# Adafruit_PiCowbell_CAN_Bus.net
KiCad netlist of a schematic drawn in EAGLE
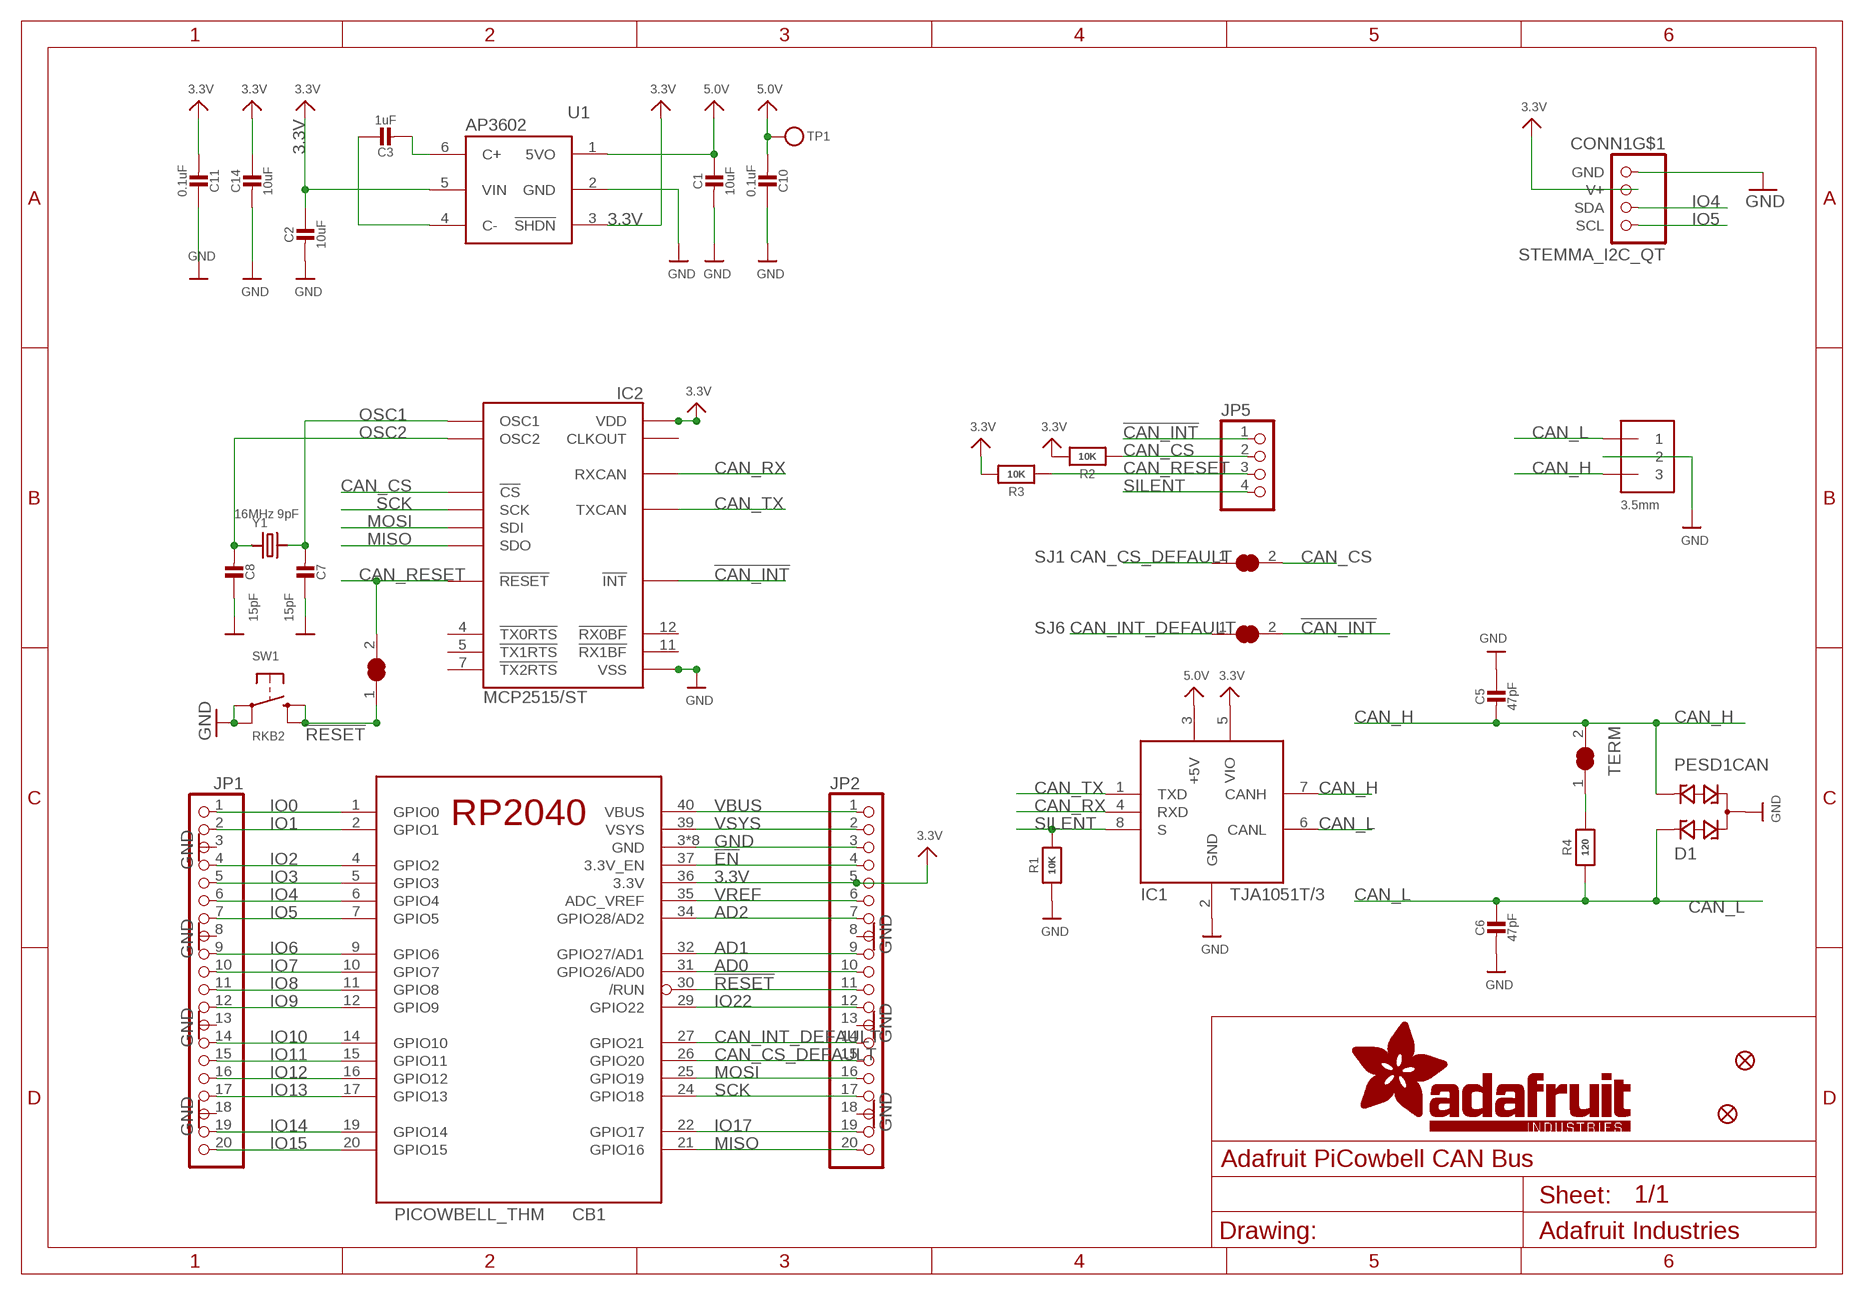
[diagram p0: schematic, sheet 1]

(export (version "E")
  (design (tool "Eeschema 10.0.6"))
  (components
    (comp (ref "C1")
      (value "10uF")
      (footprint "eagle-import:0805-NO")
      (libsource (lib "eagle-import") (part "CAP_CERAMIC0805-NOOUTLINE"))
    )
    (comp (ref "C2")
      (value "10uF")
      (footprint "eagle-import:0805-NO")
      (libsource (lib "eagle-import") (part "CAP_CERAMIC0805-NOOUTLINE"))
    )
    (comp (ref "C3")
      (value "1uF")
      (footprint "eagle-import:0805-NO")
      (libsource (lib "eagle-import") (part "CAP_CERAMIC0805-NOOUTLINE"))
    )
    (comp (ref "C5")
      (value "47pF")
      (footprint "eagle-import:0603-NO")
      (libsource (lib "eagle-import") (part "CAP_CERAMIC0603_NO"))
    )
    (comp (ref "C6")
      (value "47pF")
      (footprint "eagle-import:0603-NO")
      (libsource (lib "eagle-import") (part "CAP_CERAMIC0603_NO"))
    )
    (comp (ref "C7")
      (value "15pF")
      (footprint "eagle-import:0603-NO")
      (libsource (lib "eagle-import") (part "CAP_CERAMIC0603_NO"))
    )
    (comp (ref "C8")
      (value "15pF")
      (footprint "eagle-import:0603-NO")
      (libsource (lib "eagle-import") (part "CAP_CERAMIC0603_NO"))
    )
    (comp (ref "C10")
      (value "0.1uF")
      (footprint "eagle-import:0603-NO")
      (libsource (lib "eagle-import") (part "CAP_CERAMIC0603_NO"))
    )
    (comp (ref "C11")
      (value "0.1uF")
      (footprint "eagle-import:0603-NO")
      (libsource (lib "eagle-import") (part "CAP_CERAMIC0603_NO"))
    )
    (comp (ref "C14")
      (value "10uF")
      (footprint "eagle-import:0805-NO")
      (libsource (lib "eagle-import") (part "CAP_CERAMIC0805-NOOUTLINE"))
    )
    (comp (ref "CAN")
      (value "3.5mm")
      (footprint "eagle-import:TERMBLOCK_1X3-3.5MM")
      (libsource (lib "eagle-import") (part "TERMBLOCK_1X3"))
    )
    (comp (ref "CB1")
      (value "PICOWBELL_THM")
      (footprint "eagle-import:PICOWBELL_THM")
      (libsource (lib "eagle-import") (part "PICOWBELL_THM"))
    )
    (comp (ref "CONN1")
      (value "STEMMA_I2C_QT")
      (footprint "eagle-import:JST_SH4")
      (libsource (lib "eagle-import") (part "STEMMA_I2C_QT"))
    )
    (comp (ref "D1")
      (value "PESD1CAN")
      (footprint "eagle-import:SOT23")
      (libsource (lib "eagle-import") (part "PESD1CAN"))
    )
    (comp (ref "FID1")
      (value "FIDUCIAL_1MM")
      (footprint "eagle-import:FIDUCIAL_1MM")
      (libsource (lib "eagle-import") (part "FIDUCIAL_1MM"))
    )
    (comp (ref "FID2")
      (value "FIDUCIAL_1MM")
      (footprint "eagle-import:FIDUCIAL_1MM")
      (libsource (lib "eagle-import") (part "FIDUCIAL_1MM"))
    )
    (comp (ref "IC1")
      (value "TJA1051T/3")
      (footprint "eagle-import:SOIC8_150MIL")
      (libsource (lib "eagle-import") (part "CAN_TRANSCIEVER_TCAN1051V"))
    )
    (comp (ref "IC2")
      (value "MCP2515/ST")
      (footprint "eagle-import:SSOP20")
      (libsource (lib "eagle-import") (part "MCP2515/ST"))
    )
    (comp (ref "JP1")
      (value "HEADER-1X20_70MIL")
      (footprint "eagle-import:1X20_ROUND_70MIL")
      (libsource (lib "eagle-import") (part "HEADER-1X20_70MIL"))
    )
    (comp (ref "JP2")
      (value "HEADER-1X20_70MIL")
      (footprint "eagle-import:1X20_ROUND_70MIL")
      (libsource (lib "eagle-import") (part "HEADER-1X20_70MIL"))
    )
    (comp (ref "JP5")
      (value "HEADER-1X4ROUND")
      (footprint "eagle-import:1X04_ROUND")
      (libsource (lib "eagle-import") (part "HEADER-1X4ROUND"))
    )
    (comp (ref "R1")
      (value "10K")
      (footprint "eagle-import:0603-NO")
      (libsource (lib "eagle-import") (part "RESISTOR_0603_NOOUT"))
    )
    (comp (ref "R2")
      (value "10K")
      (footprint "eagle-import:0603-NO")
      (libsource (lib "eagle-import") (part "RESISTOR_0603_NOOUT"))
    )
    (comp (ref "R3")
      (value "10K")
      (footprint "eagle-import:0603-NO")
      (libsource (lib "eagle-import") (part "RESISTOR_0603_NOOUT"))
    )
    (comp (ref "R4")
      (value "120")
      (footprint "eagle-import:0603-NO")
      (libsource (lib "eagle-import") (part "RESISTOR_0603_NOOUT"))
    )
    (comp (ref "SJ1")
      (value "SOLDERJUMPER_CLOSED")
      (footprint "eagle-import:SOLDERJUMPER_CLOSEDWIRE")
      (libsource (lib "eagle-import") (part "SOLDERJUMPER_CLOSED"))
    )
    (comp (ref "SJ5")
      (value "SOLDERJUMPER_CLOSED")
      (footprint "eagle-import:SOLDERJUMPER_CLOSEDWIRE")
      (libsource (lib "eagle-import") (part "SOLDERJUMPER_CLOSED"))
    )
    (comp (ref "SJ6")
      (value "SOLDERJUMPER_CLOSED")
      (footprint "eagle-import:SOLDERJUMPER_CLOSEDWIRE")
      (libsource (lib "eagle-import") (part "SOLDERJUMPER_CLOSED"))
    )
    (comp (ref "SW1")
      (value "RKB2")
      (footprint "eagle-import:BTN_RKB2_4.6X2.8")
      (libsource (lib "eagle-import") (part "SWITCH_TACT_SMT_RKB2"))
    )
    (comp (ref "TERM")
      (value "SOLDERJUMPER_CLOSED")
      (footprint "eagle-import:SOLDERJUMPER_CLOSEDWIRE")
      (libsource (lib "eagle-import") (part "SOLDERJUMPER_CLOSED"))
    )
    (comp (ref "TP1")
      (value "TESTPOINTROUND1.5MM")
      (footprint "eagle-import:TESTPOINT_ROUND_1.5MM")
      (libsource (lib "eagle-import") (part "TESTPOINTROUND1.5MM"))
    )
    (comp (ref "U1")
      (value "AP3602")
      (footprint "eagle-import:SOT23-6")
      (libsource (lib "eagle-import") (part "AP3602"))
    )
    (comp (ref "Y1")
      (value "16MHz 9pF")
      (footprint "eagle-import:CRYSTAL_3.2X2.5")
      (libsource (lib "eagle-import") (part "CRYSTAL3.2X2.5"))
    )
  )
  (nets
    (net (code "1") (name "/AD0") (class "Default")
      (node (ref "CB1") (pin "31") (pinfunction "GPIO26/AD0_31") (pintype "bidirectional"))
      (node (ref "JP2") (pin "10") (pinfunction "10_10") (pintype "passive"))
    )
    (net (code "2") (name "/AD1") (class "Default")
      (node (ref "CB1") (pin "32") (pinfunction "GPIO27/AD1_32") (pintype "bidirectional"))
      (node (ref "JP2") (pin "9") (pinfunction "9_9") (pintype "passive"))
    )
    (net (code "3") (name "/AD2") (class "Default")
      (node (ref "CB1") (pin "34") (pinfunction "GPIO28/AD2_34") (pintype "bidirectional"))
      (node (ref "JP2") (pin "7") (pinfunction "7_7") (pintype "passive"))
    )
    (net (code "4") (name "/CAN_CS") (class "Default")
      (node (ref "IC2") (pin "18") (pinfunction "~{CS}_18") (pintype "input"))
      (node (ref "JP5") (pin "2") (pinfunction "2_2") (pintype "passive"))
      (node (ref "R2") (pin "1") (pinfunction "1_1") (pintype "passive"))
      (node (ref "SJ1") (pin "2") (pinfunction "2_2") (pintype "passive"))
    )
    (net (code "5") (name "/CAN_CS_DEFAULT") (class "Default")
      (node (ref "CB1") (pin "26") (pinfunction "GPIO20_26") (pintype "bidirectional"))
      (node (ref "JP2") (pin "15") (pinfunction "15_15") (pintype "passive"))
      (node (ref "SJ1") (pin "1") (pinfunction "1_1") (pintype "passive"))
    )
    (net (code "6") (name "/CAN_H") (class "Default")
      (node (ref "C5") (pin "2") (pinfunction "2_2") (pintype "passive"))
      (node (ref "CAN") (pin "3") (pinfunction "3_3") (pintype "passive"))
      (node (ref "D1") (pin "2") (pinfunction "2_2") (pintype "passive"))
      (node (ref "IC1") (pin "7") (pinfunction "CANH_7") (pintype "bidirectional"))
      (node (ref "TERM") (pin "2") (pinfunction "2_2") (pintype "passive"))
    )
    (net (code "7") (name "/CAN_INT_DEFAULT") (class "Default")
      (node (ref "CB1") (pin "27") (pinfunction "GPIO21_27") (pintype "bidirectional"))
      (node (ref "JP2") (pin "14") (pinfunction "14_14") (pintype "passive"))
      (node (ref "SJ6") (pin "1") (pinfunction "1_1") (pintype "passive"))
    )
    (net (code "8") (name "/CAN_L") (class "Default")
      (node (ref "C6") (pin "1") (pinfunction "1_1") (pintype "passive"))
      (node (ref "CAN") (pin "1") (pinfunction "1_1") (pintype "passive"))
      (node (ref "D1") (pin "1") (pinfunction "1_1") (pintype "passive"))
      (node (ref "IC1") (pin "6") (pinfunction "CANL_6") (pintype "bidirectional"))
      (node (ref "R4") (pin "1") (pinfunction "1_1") (pintype "passive"))
    )
    (net (code "9") (name "/CAN_RESET") (class "Default")
      (node (ref "IC2") (pin "19") (pinfunction "~{RESET}_19") (pintype "input"))
      (node (ref "JP5") (pin "3") (pinfunction "3_3") (pintype "passive"))
      (node (ref "R3") (pin "1") (pinfunction "1_1") (pintype "passive"))
      (node (ref "SJ5") (pin "2") (pinfunction "2_2") (pintype "passive"))
    )
    (net (code "10") (name "/CAN_RX") (class "Default")
      (node (ref "IC1") (pin "4") (pinfunction "RXD_4") (pintype "output"))
      (node (ref "IC2") (pin "2") (pinfunction "RXCAN_2") (pintype "bidirectional"))
    )
    (net (code "11") (name "/CAN_TX") (class "Default")
      (node (ref "IC1") (pin "1") (pinfunction "TXD_1") (pintype "input"))
      (node (ref "IC2") (pin "1") (pinfunction "TXCAN_1") (pintype "bidirectional"))
    )
    (net (code "12") (name "/IO0") (class "Default")
      (node (ref "CB1") (pin "1") (pinfunction "GPIO0_1") (pintype "bidirectional"))
      (node (ref "JP1") (pin "1") (pinfunction "1_1") (pintype "passive"))
    )
    (net (code "13") (name "/IO1") (class "Default")
      (node (ref "CB1") (pin "2") (pinfunction "GPIO1_2") (pintype "bidirectional"))
      (node (ref "JP1") (pin "2") (pinfunction "2_2") (pintype "passive"))
    )
    (net (code "14") (name "/IO2") (class "Default")
      (node (ref "CB1") (pin "4") (pinfunction "GPIO2_4") (pintype "bidirectional"))
      (node (ref "JP1") (pin "4") (pinfunction "4_4") (pintype "passive"))
    )
    (net (code "15") (name "/IO3") (class "Default")
      (node (ref "CB1") (pin "5") (pinfunction "GPIO3_5") (pintype "bidirectional"))
      (node (ref "JP1") (pin "5") (pinfunction "5_5") (pintype "passive"))
    )
    (net (code "16") (name "/IO4") (class "Default")
      (node (ref "CB1") (pin "6") (pinfunction "GPIO4_6") (pintype "bidirectional"))
      (node (ref "CONN1") (pin "3") (pinfunction "SDA_3") (pintype "passive"))
      (node (ref "JP1") (pin "6") (pinfunction "6_6") (pintype "passive"))
    )
    (net (code "17") (name "/IO5") (class "Default")
      (node (ref "CB1") (pin "7") (pinfunction "GPIO5_7") (pintype "bidirectional"))
      (node (ref "CONN1") (pin "4") (pinfunction "SCL_4") (pintype "passive"))
      (node (ref "JP1") (pin "7") (pinfunction "7_7") (pintype "passive"))
    )
    (net (code "18") (name "/IO6") (class "Default")
      (node (ref "CB1") (pin "9") (pinfunction "GPIO6_9") (pintype "bidirectional"))
      (node (ref "JP1") (pin "9") (pinfunction "9_9") (pintype "passive"))
    )
    (net (code "19") (name "/IO7") (class "Default")
      (node (ref "CB1") (pin "10") (pinfunction "GPIO7_10") (pintype "bidirectional"))
      (node (ref "JP1") (pin "10") (pinfunction "10_10") (pintype "passive"))
    )
    (net (code "20") (name "/IO8") (class "Default")
      (node (ref "CB1") (pin "11") (pinfunction "GPIO8_11") (pintype "bidirectional"))
      (node (ref "JP1") (pin "11") (pinfunction "11_11") (pintype "passive"))
    )
    (net (code "21") (name "/IO9") (class "Default")
      (node (ref "CB1") (pin "12") (pinfunction "GPIO9_12") (pintype "bidirectional"))
      (node (ref "JP1") (pin "12") (pinfunction "12_12") (pintype "passive"))
    )
    (net (code "22") (name "/IO10") (class "Default")
      (node (ref "CB1") (pin "14") (pinfunction "GPIO10_14") (pintype "bidirectional"))
      (node (ref "JP1") (pin "14") (pinfunction "14_14") (pintype "passive"))
    )
    (net (code "23") (name "/IO11") (class "Default")
      (node (ref "CB1") (pin "15") (pinfunction "GPIO11_15") (pintype "bidirectional"))
      (node (ref "JP1") (pin "15") (pinfunction "15_15") (pintype "passive"))
    )
    (net (code "24") (name "/IO12") (class "Default")
      (node (ref "CB1") (pin "16") (pinfunction "GPIO12_16") (pintype "bidirectional"))
      (node (ref "JP1") (pin "16") (pinfunction "16_16") (pintype "passive"))
    )
    (net (code "25") (name "/IO13") (class "Default")
      (node (ref "CB1") (pin "17") (pinfunction "GPIO13_17") (pintype "bidirectional"))
      (node (ref "JP1") (pin "17") (pinfunction "17_17") (pintype "passive"))
    )
    (net (code "26") (name "/IO14") (class "Default")
      (node (ref "CB1") (pin "19") (pinfunction "GPIO14_19") (pintype "bidirectional"))
      (node (ref "JP1") (pin "19") (pinfunction "19_19") (pintype "passive"))
    )
    (net (code "27") (name "/IO15") (class "Default")
      (node (ref "CB1") (pin "20") (pinfunction "GPIO15_20") (pintype "bidirectional"))
      (node (ref "JP1") (pin "20") (pinfunction "20_20") (pintype "passive"))
    )
    (net (code "28") (name "/IO17") (class "Default")
      (node (ref "CB1") (pin "22") (pinfunction "GPIO17_22") (pintype "bidirectional"))
      (node (ref "JP2") (pin "19") (pinfunction "19_19") (pintype "passive"))
    )
    (net (code "29") (name "/IO22") (class "Default")
      (node (ref "CB1") (pin "29") (pinfunction "GPIO22_29") (pintype "bidirectional"))
      (node (ref "JP2") (pin "12") (pinfunction "12_12") (pintype "passive"))
    )
    (net (code "30") (name "/MISO") (class "Default")
      (node (ref "CB1") (pin "21") (pinfunction "GPIO16_21") (pintype "bidirectional"))
      (node (ref "IC2") (pin "17") (pinfunction "SDO_17") (pintype "output"))
      (node (ref "JP2") (pin "20") (pinfunction "20_20") (pintype "passive"))
    )
    (net (code "31") (name "/MOSI") (class "Default")
      (node (ref "CB1") (pin "25") (pinfunction "GPIO19_25") (pintype "bidirectional"))
      (node (ref "IC2") (pin "16") (pinfunction "SDI_16") (pintype "input"))
      (node (ref "JP2") (pin "16") (pinfunction "16_16") (pintype "passive"))
    )
    (net (code "32") (name "/OSC1") (class "Default")
      (node (ref "C7") (pin "2") (pinfunction "2_2") (pintype "passive"))
      (node (ref "IC2") (pin "9") (pinfunction "OSC1_9") (pintype "bidirectional"))
      (node (ref "Y1") (pin "2") (pinfunction "2_2") (pintype "passive"))
    )
    (net (code "33") (name "/OSC2") (class "Default")
      (node (ref "C8") (pin "2") (pinfunction "2_2") (pintype "passive"))
      (node (ref "IC2") (pin "8") (pinfunction "OSC2_8") (pintype "bidirectional"))
      (node (ref "Y1") (pin "1") (pinfunction "1_1") (pintype "passive"))
    )
    (net (code "34") (name "/SCK") (class "Default")
      (node (ref "CB1") (pin "24") (pinfunction "GPIO18_24") (pintype "bidirectional"))
      (node (ref "IC2") (pin "14") (pinfunction "SCK_14") (pintype "input"))
      (node (ref "JP2") (pin "17") (pinfunction "17_17") (pintype "passive"))
    )
    (net (code "35") (name "/SILENT") (class "Default")
      (node (ref "IC1") (pin "8") (pinfunction "S_8") (pintype "input"))
      (node (ref "JP5") (pin "4") (pinfunction "4_4") (pintype "passive"))
      (node (ref "R1") (pin "2") (pinfunction "2_2") (pintype "passive"))
    )
    (net (code "36") (name "/VBUS") (class "Default")
      (node (ref "CB1") (pin "40") (pinfunction "VBUS_40") (pintype "power_in"))
      (node (ref "JP2") (pin "1") (pinfunction "1_1") (pintype "passive"))
    )
    (net (code "37") (name "/VREF") (class "Default")
      (node (ref "CB1") (pin "35") (pinfunction "ADC_VREF_35") (pintype "passive"))
      (node (ref "JP2") (pin "6") (pinfunction "6_6") (pintype "passive"))
    )
    (net (code "38") (name "/VSYS") (class "Default")
      (node (ref "CB1") (pin "39") (pinfunction "VSYS_39") (pintype "power_in"))
      (node (ref "JP2") (pin "2") (pinfunction "2_2") (pintype "passive"))
    )
    (net (code "39") (name "/~{CAN_INT}") (class "Default")
      (node (ref "IC2") (pin "13") (pinfunction "~{INT}_13") (pintype "bidirectional"))
      (node (ref "JP5") (pin "1") (pinfunction "1_1") (pintype "passive"))
      (node (ref "SJ6") (pin "2") (pinfunction "2_2") (pintype "passive"))
    )
    (net (code "40") (name "/~{EN}") (class "Default")
      (node (ref "CB1") (pin "37") (pinfunction "3.3V_EN_37") (pintype "passive"))
      (node (ref "JP2") (pin "4") (pinfunction "4_4") (pintype "passive"))
    )
    (net (code "41") (name "/~{RESET}") (class "Default")
      (node (ref "CB1") (pin "30") (pinfunction "/RUN_30") (pintype "bidirectional"))
      (node (ref "JP2") (pin "11") (pinfunction "11_11") (pintype "passive"))
      (node (ref "SJ5") (pin "1") (pinfunction "1_1") (pintype "passive"))
      (node (ref "SW1") (pin "B") (pinfunction "S_B") (pintype "passive"))
      (node (ref "SW1") (pin "B'") (pinfunction "S1_B'") (pintype "passive"))
    )
    (net (code "42") (name "3.3V") (class "Default")
      (node (ref "C11") (pin "2") (pinfunction "2_2") (pintype "passive"))
      (node (ref "C14") (pin "1") (pinfunction "1_1") (pintype "passive"))
      (node (ref "C2") (pin "1") (pinfunction "1_1") (pintype "passive"))
      (node (ref "CB1") (pin "36") (pinfunction "3.3V_36") (pintype "power_in"))
      (node (ref "CONN1") (pin "2") (pinfunction "V+_2") (pintype "passive"))
      (node (ref "IC1") (pin "5") (pinfunction "VIO_5") (pintype "power_in"))
      (node (ref "IC2") (pin "20") (pinfunction "VDD_20") (pintype "power_in"))
      (node (ref "JP2") (pin "5") (pinfunction "5_5") (pintype "passive"))
      (node (ref "R2") (pin "2") (pinfunction "2_2") (pintype "passive"))
      (node (ref "R3") (pin "2") (pinfunction "2_2") (pintype "passive"))
      (node (ref "U1") (pin "3") (pinfunction "~{SHDN}_3") (pintype "input"))
      (node (ref "U1") (pin "5") (pinfunction "VIN_5") (pintype "power_in"))
    )
    (net (code "43") (name "5.0V") (class "Default")
      (node (ref "C1") (pin "1") (pinfunction "1_1") (pintype "passive"))
      (node (ref "C10") (pin "2") (pinfunction "2_2") (pintype "passive"))
      (node (ref "IC1") (pin "3") (pinfunction "+5V_3") (pintype "power_in"))
      (node (ref "TP1") (pin "P$1") (pinfunction "P$1_P$1") (pintype "bidirectional"))
      (node (ref "U1") (pin "1") (pinfunction "5VO_1") (pintype "power_in"))
    )
    (net (code "44") (name "GND") (class "Default")
      (node (ref "C1") (pin "2") (pinfunction "2_2") (pintype "passive"))
      (node (ref "C10") (pin "1") (pinfunction "1_1") (pintype "passive"))
      (node (ref "C11") (pin "1") (pinfunction "1_1") (pintype "passive"))
      (node (ref "C14") (pin "2") (pinfunction "2_2") (pintype "passive"))
      (node (ref "C2") (pin "2") (pinfunction "2_2") (pintype "passive"))
      (node (ref "C5") (pin "1") (pinfunction "1_1") (pintype "passive"))
      (node (ref "C6") (pin "2") (pinfunction "2_2") (pintype "passive"))
      (node (ref "C7") (pin "1") (pinfunction "1_1") (pintype "passive"))
      (node (ref "C8") (pin "1") (pinfunction "1_1") (pintype "passive"))
      (node (ref "CAN") (pin "2") (pinfunction "2_2") (pintype "passive"))
      (node (ref "CB1") (pin "13") (pinfunction "GND_13") (pintype "power_in"))
      (node (ref "CB1") (pin "18") (pinfunction "GND_18") (pintype "power_in"))
      (node (ref "CB1") (pin "23") (pinfunction "GND_23") (pintype "power_in"))
      (node (ref "CB1") (pin "28") (pinfunction "GND_28") (pintype "power_in"))
      (node (ref "CB1") (pin "3") (pinfunction "GND_3") (pintype "power_in"))
      (node (ref "CB1") (pin "33") (pinfunction "GND_33") (pintype "power_in"))
      (node (ref "CB1") (pin "38") (pinfunction "GND_38") (pintype "power_in"))
      (node (ref "CB1") (pin "8") (pinfunction "GND_8") (pintype "power_in"))
      (node (ref "CONN1") (pin "1") (pinfunction "GND_1") (pintype "passive"))
      (node (ref "D1") (pin "3") (pinfunction "3_3") (pintype "passive"))
      (node (ref "IC1") (pin "2") (pinfunction "GND_2") (pintype "power_in"))
      (node (ref "IC2") (pin "10") (pinfunction "VSS_10") (pintype "power_in"))
      (node (ref "JP1") (pin "13") (pinfunction "13_13") (pintype "passive"))
      (node (ref "JP1") (pin "18") (pinfunction "18_18") (pintype "passive"))
      (node (ref "JP1") (pin "3") (pinfunction "3_3") (pintype "passive"))
      (node (ref "JP1") (pin "8") (pinfunction "8_8") (pintype "passive"))
      (node (ref "JP2") (pin "13") (pinfunction "13_13") (pintype "passive"))
      (node (ref "JP2") (pin "18") (pinfunction "18_18") (pintype "passive"))
      (node (ref "JP2") (pin "3") (pinfunction "3_3") (pintype "passive"))
      (node (ref "JP2") (pin "8") (pinfunction "8_8") (pintype "passive"))
      (node (ref "R1") (pin "1") (pinfunction "1_1") (pintype "passive"))
      (node (ref "SW1") (pin "A") (pinfunction "P_A") (pintype "passive"))
      (node (ref "SW1") (pin "A'") (pinfunction "P1_A'") (pintype "passive"))
      (node (ref "U1") (pin "2") (pinfunction "GND_2") (pintype "power_in"))
    )
    (net (code "45") (name "Net-(R4-Pad2)") (class "Default")
      (node (ref "R4") (pin "2") (pinfunction "2_2") (pintype "passive"))
      (node (ref "TERM") (pin "1") (pinfunction "1_1") (pintype "passive"))
    )
    (net (code "46") (name "Net-(U1-C+)") (class "Default")
      (node (ref "C3") (pin "2") (pinfunction "2_2") (pintype "passive"))
      (node (ref "U1") (pin "6") (pinfunction "C+_6") (pintype "bidirectional"))
    )
    (net (code "47") (name "Net-(U1-C-)") (class "Default")
      (node (ref "C3") (pin "1") (pinfunction "1_1") (pintype "passive"))
      (node (ref "U1") (pin "4") (pinfunction "C-_4") (pintype "bidirectional"))
    )
    (net (code "48") (name "unconnected-(IC2-CLKOUT-Pad3)") (class "Default")
      (node (ref "IC2") (pin "3") (pinfunction "CLKOUT_3") (pintype "output"))
    )
    (net (code "49") (name "unconnected-(IC2-~{RX0BF}-Pad12)") (class "Default")
      (node (ref "IC2") (pin "12") (pinfunction "~{RX0BF}_12") (pintype "bidirectional"))
    )
    (net (code "50") (name "unconnected-(IC2-~{RX1BF}-Pad11)") (class "Default")
      (node (ref "IC2") (pin "11") (pinfunction "~{RX1BF}_11") (pintype "bidirectional"))
    )
    (net (code "51") (name "unconnected-(IC2-~{TX0RTS}-Pad4)") (class "Default")
      (node (ref "IC2") (pin "4") (pinfunction "~{TX0RTS}_4") (pintype "bidirectional"))
    )
    (net (code "52") (name "unconnected-(IC2-~{TX1RTS}-Pad5)") (class "Default")
      (node (ref "IC2") (pin "5") (pinfunction "~{TX1RTS}_5") (pintype "bidirectional"))
    )
    (net (code "53") (name "unconnected-(IC2-~{TX2RTS}-Pad7)") (class "Default")
      (node (ref "IC2") (pin "7") (pinfunction "~{TX2RTS}_7") (pintype "bidirectional"))
    )
  )
)
